# MDM_V3_ControlBoard_B.net
KiCad netlist of a schematic drawn in EAGLE
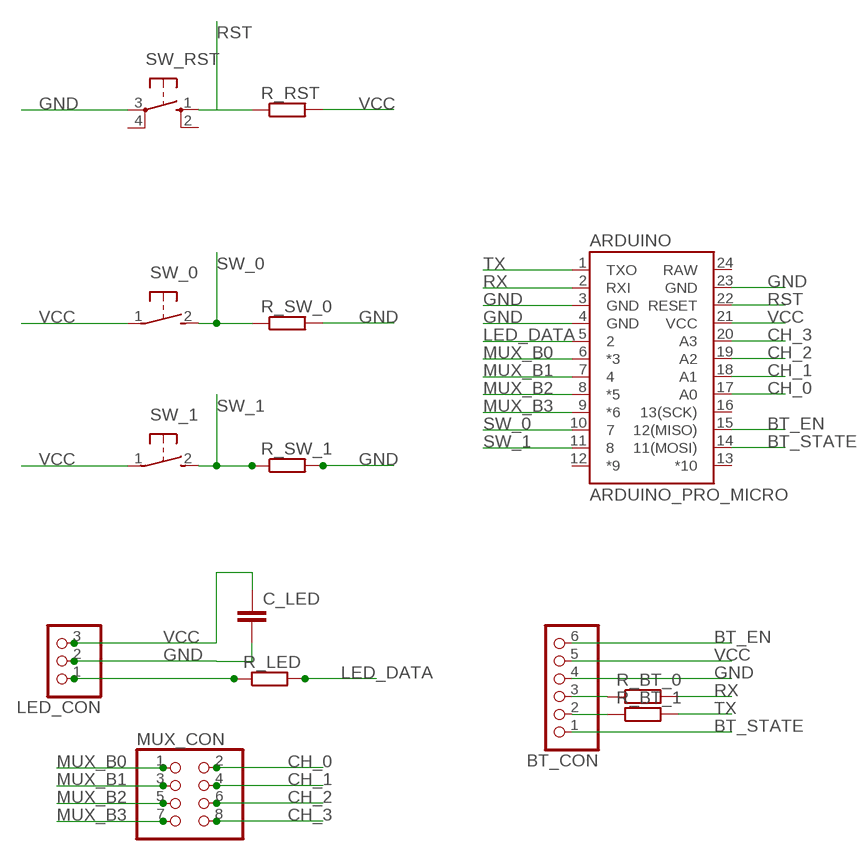
[diagram p0: schematic, sheet 1]

(export (version "E")
  (design (tool "Eeschema 10.0.6"))
  (components
    (comp (ref "ARDUINO")
      (value "ARDUINO_PRO_MICRO")
      (footprint "eagle-import:ARDUINO_PRO_MICRO")
      (libsource (lib "eagle-import") (part "ARDUINO_PRO_MICRO"))
    )
    (comp (ref "BT_CON")
      (value "PINHD-1X6")
      (footprint "eagle-import:1X06")
      (libsource (lib "eagle-import") (part "PINHD-1X6"))
    )
    (comp (ref "C_LED")
      (value "C-EUC1206K")
      (footprint "eagle-import:C1206K")
      (libsource (lib "eagle-import") (part "C-EUC1206K"))
    )
    (comp (ref "LED_CON")
      (value "PINHD-1X3")
      (footprint "eagle-import:1X03")
      (libsource (lib "eagle-import") (part "PINHD-1X3"))
    )
    (comp (ref "MUX_CON")
      (value "PINHD-2X4")
      (footprint "eagle-import:2X04")
      (libsource (lib "eagle-import") (part "PINHD-2X4"))
    )
    (comp (ref "R_BT_0")
      (value "R-EU_M1206")
      (footprint "eagle-import:M1206")
      (libsource (lib "eagle-import") (part "R-EU_M1206"))
    )
    (comp (ref "R_BT_1")
      (value "R-EU_M1206")
      (footprint "eagle-import:M1206")
      (libsource (lib "eagle-import") (part "R-EU_M1206"))
    )
    (comp (ref "R_LED")
      (value "R-EU_M1206")
      (footprint "eagle-import:M1206")
      (libsource (lib "eagle-import") (part "R-EU_M1206"))
    )
    (comp (ref "R_RST")
      (value "R-EU_M1206")
      (footprint "eagle-import:M1206")
      (libsource (lib "eagle-import") (part "R-EU_M1206"))
    )
    (comp (ref "R_SW_0")
      (value "R-EU_M1206")
      (footprint "eagle-import:M1206")
      (libsource (lib "eagle-import") (part "R-EU_M1206"))
    )
    (comp (ref "R_SW_1")
      (value "R-EU_M1206")
      (footprint "eagle-import:M1206")
      (libsource (lib "eagle-import") (part "R-EU_M1206"))
    )
    (comp (ref "SW_0")
      (value "31-XX")
      (footprint "eagle-import:B3F-31XX")
      (fields (field (name "MPN") "B3F-3100"))
      (libsource (lib "eagle-import") (part "31-XX"))
    )
    (comp (ref "SW_1")
      (value "31-XX")
      (footprint "eagle-import:B3F-31XX")
      (fields (field (name "MPN") "B3F-3100"))
      (libsource (lib "eagle-import") (part "31-XX"))
    )
    (comp (ref "SW_RST")
      (value "10-XX")
      (footprint "eagle-import:B3F-10XX")
      (fields (field (name "MPN") "B3F-1000"))
      (libsource (lib "eagle-import") (part "10-XX"))
    )
  )
  (nets
    (net (code "1") (name "/BT_EN") (class "Default")
      (node (ref "ARDUINO") (pin "15") (pinfunction "12(MISO)_15") (pintype "bidirectional"))
      (node (ref "BT_CON") (pin "6") (pinfunction "6_6") (pintype "passive"))
    )
    (net (code "2") (name "/BT_STATE") (class "Default")
      (node (ref "ARDUINO") (pin "14") (pinfunction "11(MOSI)_14") (pintype "bidirectional"))
      (node (ref "BT_CON") (pin "1") (pinfunction "1_1") (pintype "passive"))
    )
    (net (code "3") (name "/CH_0") (class "Default")
      (node (ref "ARDUINO") (pin "17") (pinfunction "A0_17") (pintype "bidirectional"))
      (node (ref "MUX_CON") (pin "2") (pinfunction "2_2") (pintype "passive"))
    )
    (net (code "4") (name "/CH_1") (class "Default")
      (node (ref "ARDUINO") (pin "18") (pinfunction "A1_18") (pintype "bidirectional"))
      (node (ref "MUX_CON") (pin "4") (pinfunction "4_4") (pintype "passive"))
    )
    (net (code "5") (name "/CH_2") (class "Default")
      (node (ref "ARDUINO") (pin "19") (pinfunction "A2_19") (pintype "bidirectional"))
      (node (ref "MUX_CON") (pin "6") (pinfunction "6_6") (pintype "passive"))
    )
    (net (code "6") (name "/CH_3") (class "Default")
      (node (ref "ARDUINO") (pin "20") (pinfunction "A3_20") (pintype "bidirectional"))
      (node (ref "MUX_CON") (pin "8") (pinfunction "8_8") (pintype "passive"))
    )
    (net (code "7") (name "/GND") (class "Default")
      (node (ref "ARDUINO") (pin "23") (pinfunction "GND_23") (pintype "bidirectional"))
      (node (ref "ARDUINO") (pin "3") (pinfunction "GND_3") (pintype "bidirectional"))
      (node (ref "ARDUINO") (pin "4") (pinfunction "GND_4") (pintype "bidirectional"))
      (node (ref "BT_CON") (pin "4") (pinfunction "4_4") (pintype "passive"))
      (node (ref "C_LED") (pin "2") (pinfunction "2_2") (pintype "passive"))
      (node (ref "LED_CON") (pin "2") (pinfunction "2_2") (pintype "passive"))
      (node (ref "R_SW_0") (pin "2") (pinfunction "2_2") (pintype "passive"))
      (node (ref "R_SW_1") (pin "2") (pinfunction "2_2") (pintype "passive"))
      (node (ref "SW_RST") (pin "3") (pinfunction "P_3") (pintype "passive"))
    )
    (net (code "8") (name "/LED_DATA") (class "Default")
      (node (ref "ARDUINO") (pin "5") (pinfunction "2_5") (pintype "bidirectional"))
      (node (ref "R_LED") (pin "2") (pinfunction "2_2") (pintype "passive"))
    )
    (net (code "9") (name "/MUX_B0") (class "Default")
      (node (ref "ARDUINO") (pin "6") (pinfunction "*3_6") (pintype "bidirectional"))
      (node (ref "MUX_CON") (pin "1") (pinfunction "1_1") (pintype "passive"))
    )
    (net (code "10") (name "/MUX_B1") (class "Default")
      (node (ref "ARDUINO") (pin "7") (pinfunction "4_7") (pintype "bidirectional"))
      (node (ref "MUX_CON") (pin "3") (pinfunction "3_3") (pintype "passive"))
    )
    (net (code "11") (name "/MUX_B2") (class "Default")
      (node (ref "ARDUINO") (pin "8") (pinfunction "*5_8") (pintype "bidirectional"))
      (node (ref "MUX_CON") (pin "5") (pinfunction "5_5") (pintype "passive"))
    )
    (net (code "12") (name "/MUX_B3") (class "Default")
      (node (ref "ARDUINO") (pin "9") (pinfunction "*6_9") (pintype "bidirectional"))
      (node (ref "MUX_CON") (pin "7") (pinfunction "7_7") (pintype "passive"))
    )
    (net (code "13") (name "/RST") (class "Default")
      (node (ref "ARDUINO") (pin "22") (pinfunction "RESET_22") (pintype "bidirectional"))
      (node (ref "R_RST") (pin "1") (pinfunction "1_1") (pintype "passive"))
      (node (ref "SW_RST") (pin "1") (pinfunction "S_1") (pintype "passive"))
    )
    (net (code "14") (name "/RX") (class "Default")
      (node (ref "ARDUINO") (pin "2") (pinfunction "RXI_2") (pintype "bidirectional"))
      (node (ref "R_BT_0") (pin "2") (pinfunction "2_2") (pintype "passive"))
    )
    (net (code "15") (name "/SW_0") (class "Default")
      (node (ref "ARDUINO") (pin "10") (pinfunction "7_10") (pintype "bidirectional"))
      (node (ref "R_SW_0") (pin "1") (pinfunction "1_1") (pintype "passive"))
      (node (ref "SW_0") (pin "2") (pinfunction "S_2") (pintype "passive"))
    )
    (net (code "16") (name "/SW_1") (class "Default")
      (node (ref "ARDUINO") (pin "11") (pinfunction "8_11") (pintype "bidirectional"))
      (node (ref "R_SW_1") (pin "1") (pinfunction "1_1") (pintype "passive"))
      (node (ref "SW_1") (pin "2") (pinfunction "S_2") (pintype "passive"))
    )
    (net (code "17") (name "/TX") (class "Default")
      (node (ref "ARDUINO") (pin "1") (pinfunction "TXO_1") (pintype "bidirectional"))
      (node (ref "R_BT_1") (pin "2") (pinfunction "2_2") (pintype "passive"))
    )
    (net (code "18") (name "/VCC") (class "Default")
      (node (ref "ARDUINO") (pin "21") (pinfunction "VCC_21") (pintype "bidirectional"))
      (node (ref "BT_CON") (pin "5") (pinfunction "5_5") (pintype "passive"))
      (node (ref "C_LED") (pin "1") (pinfunction "1_1") (pintype "passive"))
      (node (ref "LED_CON") (pin "3") (pinfunction "3_3") (pintype "passive"))
      (node (ref "R_RST") (pin "2") (pinfunction "2_2") (pintype "passive"))
      (node (ref "SW_0") (pin "1") (pinfunction "P_1") (pintype "passive"))
      (node (ref "SW_1") (pin "1") (pinfunction "P_1") (pintype "passive"))
    )
    (net (code "19") (name "Net-(BT_CON-Pad2)") (class "Default")
      (node (ref "BT_CON") (pin "2") (pinfunction "2_2") (pintype "passive"))
      (node (ref "R_BT_1") (pin "1") (pinfunction "1_1") (pintype "passive"))
    )
    (net (code "20") (name "Net-(BT_CON-Pad3)") (class "Default")
      (node (ref "BT_CON") (pin "3") (pinfunction "3_3") (pintype "passive"))
      (node (ref "R_BT_0") (pin "1") (pinfunction "1_1") (pintype "passive"))
    )
    (net (code "21") (name "Net-(LED_CON-Pad1)") (class "Default")
      (node (ref "LED_CON") (pin "1") (pinfunction "1_1") (pintype "passive"))
      (node (ref "R_LED") (pin "1") (pinfunction "1_1") (pintype "passive"))
    )
    (net (code "22") (name "unconnected-(ARDUINO-*9-Pad12)") (class "Default")
      (node (ref "ARDUINO") (pin "12") (pinfunction "*9_12") (pintype "bidirectional"))
    )
    (net (code "23") (name "unconnected-(ARDUINO-*10-Pad13)") (class "Default")
      (node (ref "ARDUINO") (pin "13") (pinfunction "*10_13") (pintype "bidirectional"))
    )
    (net (code "24") (name "unconnected-(ARDUINO-13(SCK)-Pad16)") (class "Default")
      (node (ref "ARDUINO") (pin "16") (pinfunction "13(SCK)_16") (pintype "bidirectional"))
    )
    (net (code "25") (name "unconnected-(ARDUINO-RAW-Pad24)") (class "Default")
      (node (ref "ARDUINO") (pin "24") (pinfunction "RAW_24") (pintype "bidirectional"))
    )
    (net (code "26") (name "unconnected-(SW_RST-P1-Pad4)") (class "Default")
      (node (ref "SW_RST") (pin "4") (pinfunction "P1_4") (pintype "passive"))
    )
    (net (code "27") (name "unconnected-(SW_RST-S1-Pad2)") (class "Default")
      (node (ref "SW_RST") (pin "2") (pinfunction "S1_2") (pintype "passive"))
    )
  )
)
